# PCM2906_SPDIF_Converter.net
KiCad netlist of a schematic drawn in EAGLE
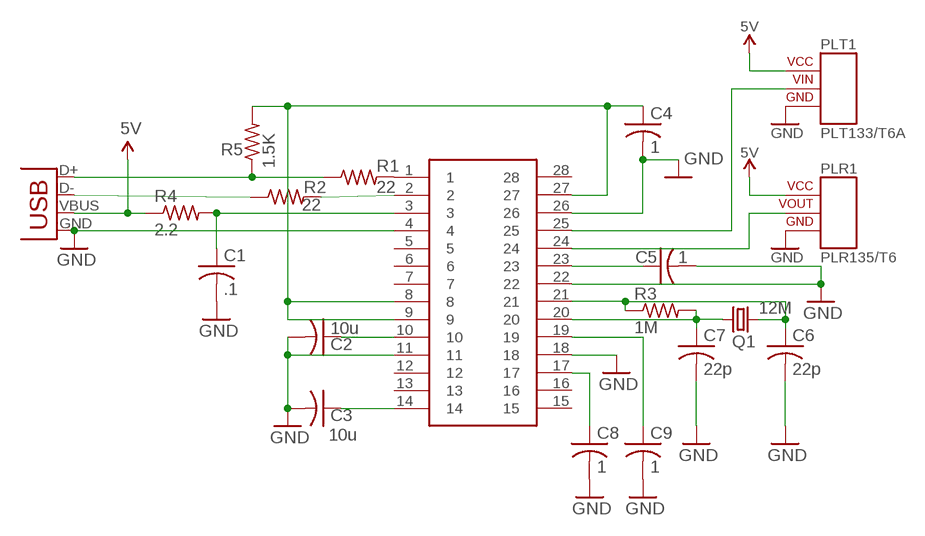
[diagram p0: schematic, sheet 1]

(export (version "E")
  (design (tool "Eeschema 10.0.6"))
  (components
    (comp (ref "C1")
      (value ".1")
      (footprint "eagle-import:C0805")
      (libsource (lib "eagle-import") (part "C-USC0805"))
    )
    (comp (ref "C2")
      (value "10u")
      (footprint "eagle-import:C1210")
      (libsource (lib "eagle-import") (part "C-USC1210"))
    )
    (comp (ref "C3")
      (value "10u")
      (footprint "eagle-import:C1210")
      (libsource (lib "eagle-import") (part "C-USC1210"))
    )
    (comp (ref "C4")
      (value "1")
      (footprint "eagle-import:C1210")
      (libsource (lib "eagle-import") (part "C-USC1210"))
    )
    (comp (ref "C5")
      (value "1")
      (footprint "eagle-import:C1210")
      (libsource (lib "eagle-import") (part "C-USC1210"))
    )
    (comp (ref "C6")
      (value "22p")
      (footprint "eagle-import:C0805")
      (libsource (lib "eagle-import") (part "C-USC0805"))
    )
    (comp (ref "C7")
      (value "22p")
      (footprint "eagle-import:C0805")
      (libsource (lib "eagle-import") (part "C-USC0805"))
    )
    (comp (ref "C8")
      (value "1")
      (footprint "eagle-import:C1210")
      (libsource (lib "eagle-import") (part "C-USC1210"))
    )
    (comp (ref "C9")
      (value "1")
      (footprint "eagle-import:C1210")
      (libsource (lib "eagle-import") (part "C-USC1210"))
    )
    (comp (ref "PCM2906")
      (value "SSOP28")
      (footprint "eagle-import:SSOP28DB")
      (libsource (lib "eagle-import") (part "SSOP28"))
    )
    (comp (ref "PLR1")
      (value "PLR135/T6")
      (footprint "eagle-import:PLR135_T6")
      (libsource (lib "eagle-import") (part "PLR135/T6"))
    )
    (comp (ref "PLT1")
      (value "PLT133/T6A")
      (footprint "eagle-import:PLT133_T6A")
      (libsource (lib "eagle-import") (part "PLT133/T6A"))
    )
    (comp (ref "Q1")
      (value "12M")
      (footprint "eagle-import:HC49US")
      (libsource (lib "eagle-import") (part "CRYSTALHC49US"))
    )
    (comp (ref "R1")
      (value "22")
      (footprint "eagle-import:R0805")
      (libsource (lib "eagle-import") (part "R-US_R0805"))
    )
    (comp (ref "R2")
      (value "22")
      (footprint "eagle-import:R0805")
      (libsource (lib "eagle-import") (part "R-US_R0805"))
    )
    (comp (ref "R3")
      (value "1M")
      (footprint "eagle-import:R0805")
      (libsource (lib "eagle-import") (part "R-US_R0805"))
    )
    (comp (ref "R4")
      (value "2.2")
      (footprint "eagle-import:R0805")
      (libsource (lib "eagle-import") (part "R-US_R0805"))
    )
    (comp (ref "R5")
      (value "1.5K")
      (footprint "eagle-import:R0805")
      (libsource (lib "eagle-import") (part "R-US_R0805"))
    )
    (comp (ref "X2")
      (value "USBSMD")
      (footprint "eagle-import:USB-MINIB")
      (libsource (lib "eagle-import") (part "USBSMD"))
    )
  )
  (nets
    (net (code "1") (name "5V") (class "Default")
      (node (ref "PLR1") (pin "VCC") (pinfunction "VCC_VCC") (pintype "power_in"))
      (node (ref "PLT1") (pin "VCC") (pinfunction "VCC_VCC") (pintype "power_in"))
      (node (ref "R4") (pin "1") (pinfunction "1_1") (pintype "passive"))
      (node (ref "X2") (pin "VBUS") (pinfunction "VBUS_VBUS") (pintype "bidirectional"))
    )
    (net (code "2") (name "GND") (class "Default")
      (node (ref "C1") (pin "2") (pinfunction "2_2") (pintype "passive"))
      (node (ref "C2") (pin "2") (pinfunction "2_2") (pintype "passive"))
      (node (ref "C3") (pin "2") (pinfunction "2_2") (pintype "passive"))
      (node (ref "C4") (pin "2") (pinfunction "2_2") (pintype "passive"))
      (node (ref "C5") (pin "2") (pinfunction "2_2") (pintype "passive"))
      (node (ref "C6") (pin "2") (pinfunction "2_2") (pintype "passive"))
      (node (ref "C7") (pin "2") (pinfunction "2_2") (pintype "passive"))
      (node (ref "C8") (pin "2") (pinfunction "2_2") (pintype "passive"))
      (node (ref "C9") (pin "2") (pinfunction "2_2") (pintype "passive"))
      (node (ref "PCM2906") (pin "11") (pinfunction "11_11") (pintype "bidirectional"))
      (node (ref "PCM2906") (pin "18") (pinfunction "18_18") (pintype "bidirectional"))
      (node (ref "PCM2906") (pin "22") (pinfunction "22_22") (pintype "bidirectional"))
      (node (ref "PCM2906") (pin "26") (pinfunction "26_26") (pintype "bidirectional"))
      (node (ref "PCM2906") (pin "4") (pinfunction "4_4") (pintype "bidirectional"))
      (node (ref "PLR1") (pin "GND") (pinfunction "GND_GND") (pintype "power_in"))
      (node (ref "PLT1") (pin "GND") (pinfunction "GND_GND") (pintype "power_in"))
      (node (ref "X2") (pin "GND") (pinfunction "GND_GND") (pintype "bidirectional"))
    )
    (net (code "3") (name "Net-(C1-Pad1)") (class "Default")
      (node (ref "C1") (pin "1") (pinfunction "1_1") (pintype "passive"))
      (node (ref "PCM2906") (pin "3") (pinfunction "3_3") (pintype "bidirectional"))
      (node (ref "R4") (pin "2") (pinfunction "2_2") (pintype "passive"))
    )
    (net (code "4") (name "Net-(C2-Pad1)") (class "Default")
      (node (ref "C2") (pin "1") (pinfunction "1_1") (pintype "passive"))
      (node (ref "PCM2906") (pin "10") (pinfunction "10_10") (pintype "bidirectional"))
    )
    (net (code "5") (name "Net-(C3-Pad1)") (class "Default")
      (node (ref "C3") (pin "1") (pinfunction "1_1") (pintype "passive"))
      (node (ref "PCM2906") (pin "14") (pinfunction "14_14") (pintype "bidirectional"))
    )
    (net (code "6") (name "Net-(C4-Pad1)") (class "Default")
      (node (ref "C4") (pin "1") (pinfunction "1_1") (pintype "passive"))
      (node (ref "PCM2906") (pin "27") (pinfunction "27_27") (pintype "bidirectional"))
      (node (ref "PCM2906") (pin "8") (pinfunction "8_8") (pintype "bidirectional"))
      (node (ref "PCM2906") (pin "9") (pinfunction "9_9") (pintype "bidirectional"))
      (node (ref "R5") (pin "2") (pinfunction "2_2") (pintype "passive"))
    )
    (net (code "7") (name "Net-(C5-Pad1)") (class "Default")
      (node (ref "C5") (pin "1") (pinfunction "1_1") (pintype "passive"))
      (node (ref "PCM2906") (pin "23") (pinfunction "23_23") (pintype "bidirectional"))
    )
    (net (code "8") (name "Net-(C6-Pad1)") (class "Default")
      (node (ref "C6") (pin "1") (pinfunction "1_1") (pintype "passive"))
      (node (ref "PCM2906") (pin "21") (pinfunction "21_21") (pintype "bidirectional"))
      (node (ref "Q1") (pin "2") (pinfunction "2_2") (pintype "passive"))
      (node (ref "R3") (pin "1") (pinfunction "1_1") (pintype "passive"))
    )
    (net (code "9") (name "Net-(C7-Pad1)") (class "Default")
      (node (ref "C7") (pin "1") (pinfunction "1_1") (pintype "passive"))
      (node (ref "PCM2906") (pin "20") (pinfunction "20_20") (pintype "bidirectional"))
      (node (ref "Q1") (pin "1") (pinfunction "1_1") (pintype "passive"))
      (node (ref "R3") (pin "2") (pinfunction "2_2") (pintype "passive"))
    )
    (net (code "10") (name "Net-(C8-Pad1)") (class "Default")
      (node (ref "C8") (pin "1") (pinfunction "1_1") (pintype "passive"))
      (node (ref "PCM2906") (pin "17") (pinfunction "17_17") (pintype "bidirectional"))
    )
    (net (code "11") (name "Net-(C9-Pad1)") (class "Default")
      (node (ref "C9") (pin "1") (pinfunction "1_1") (pintype "passive"))
      (node (ref "PCM2906") (pin "19") (pinfunction "19_19") (pintype "bidirectional"))
    )
    (net (code "12") (name "Net-(PCM2906-Pad1)") (class "Default")
      (node (ref "PCM2906") (pin "1") (pinfunction "1_1") (pintype "bidirectional"))
      (node (ref "R1") (pin "2") (pinfunction "2_2") (pintype "passive"))
    )
    (net (code "13") (name "Net-(PCM2906-Pad2)") (class "Default")
      (node (ref "PCM2906") (pin "2") (pinfunction "2_2") (pintype "bidirectional"))
      (node (ref "R2") (pin "2") (pinfunction "2_2") (pintype "passive"))
    )
    (net (code "14") (name "Net-(PCM2906-Pad24)") (class "Default")
      (node (ref "PCM2906") (pin "24") (pinfunction "24_24") (pintype "bidirectional"))
      (node (ref "PLR1") (pin "VOUT") (pinfunction "VOUT_VOUT") (pintype "bidirectional"))
    )
    (net (code "15") (name "Net-(PCM2906-Pad25)") (class "Default")
      (node (ref "PCM2906") (pin "25") (pinfunction "25_25") (pintype "bidirectional"))
      (node (ref "PLT1") (pin "VIN") (pinfunction "VIN_VIN") (pintype "bidirectional"))
    )
    (net (code "16") (name "Net-(R1-Pad1)") (class "Default")
      (node (ref "R1") (pin "1") (pinfunction "1_1") (pintype "passive"))
      (node (ref "R5") (pin "1") (pinfunction "1_1") (pintype "passive"))
      (node (ref "X2") (pin "D+") (pinfunction "D+_D+") (pintype "bidirectional"))
    )
    (net (code "17") (name "Net-(R2-Pad1)") (class "Default")
      (node (ref "R2") (pin "1") (pinfunction "1_1") (pintype "passive"))
      (node (ref "X2") (pin "D-") (pinfunction "D-_D-") (pintype "bidirectional"))
    )
    (net (code "18") (name "unconnected-(PCM2906-Pad5)") (class "Default")
      (node (ref "PCM2906") (pin "5") (pinfunction "5_5") (pintype "bidirectional"))
    )
    (net (code "19") (name "unconnected-(PCM2906-Pad6)") (class "Default")
      (node (ref "PCM2906") (pin "6") (pinfunction "6_6") (pintype "bidirectional"))
    )
    (net (code "20") (name "unconnected-(PCM2906-Pad7)") (class "Default")
      (node (ref "PCM2906") (pin "7") (pinfunction "7_7") (pintype "bidirectional"))
    )
    (net (code "21") (name "unconnected-(PCM2906-Pad12)") (class "Default")
      (node (ref "PCM2906") (pin "12") (pinfunction "12_12") (pintype "bidirectional"))
    )
    (net (code "22") (name "unconnected-(PCM2906-Pad13)") (class "Default")
      (node (ref "PCM2906") (pin "13") (pinfunction "13_13") (pintype "bidirectional"))
    )
    (net (code "23") (name "unconnected-(PCM2906-Pad15)") (class "Default")
      (node (ref "PCM2906") (pin "15") (pinfunction "15_15") (pintype "bidirectional"))
    )
    (net (code "24") (name "unconnected-(PCM2906-Pad16)") (class "Default")
      (node (ref "PCM2906") (pin "16") (pinfunction "16_16") (pintype "bidirectional"))
    )
    (net (code "25") (name "unconnected-(PCM2906-Pad28)") (class "Default")
      (node (ref "PCM2906") (pin "28") (pinfunction "28_28") (pintype "bidirectional"))
    )
  )
)
